# fountainPCB_v3.net
KiCad netlist of a schematic drawn in EAGLE
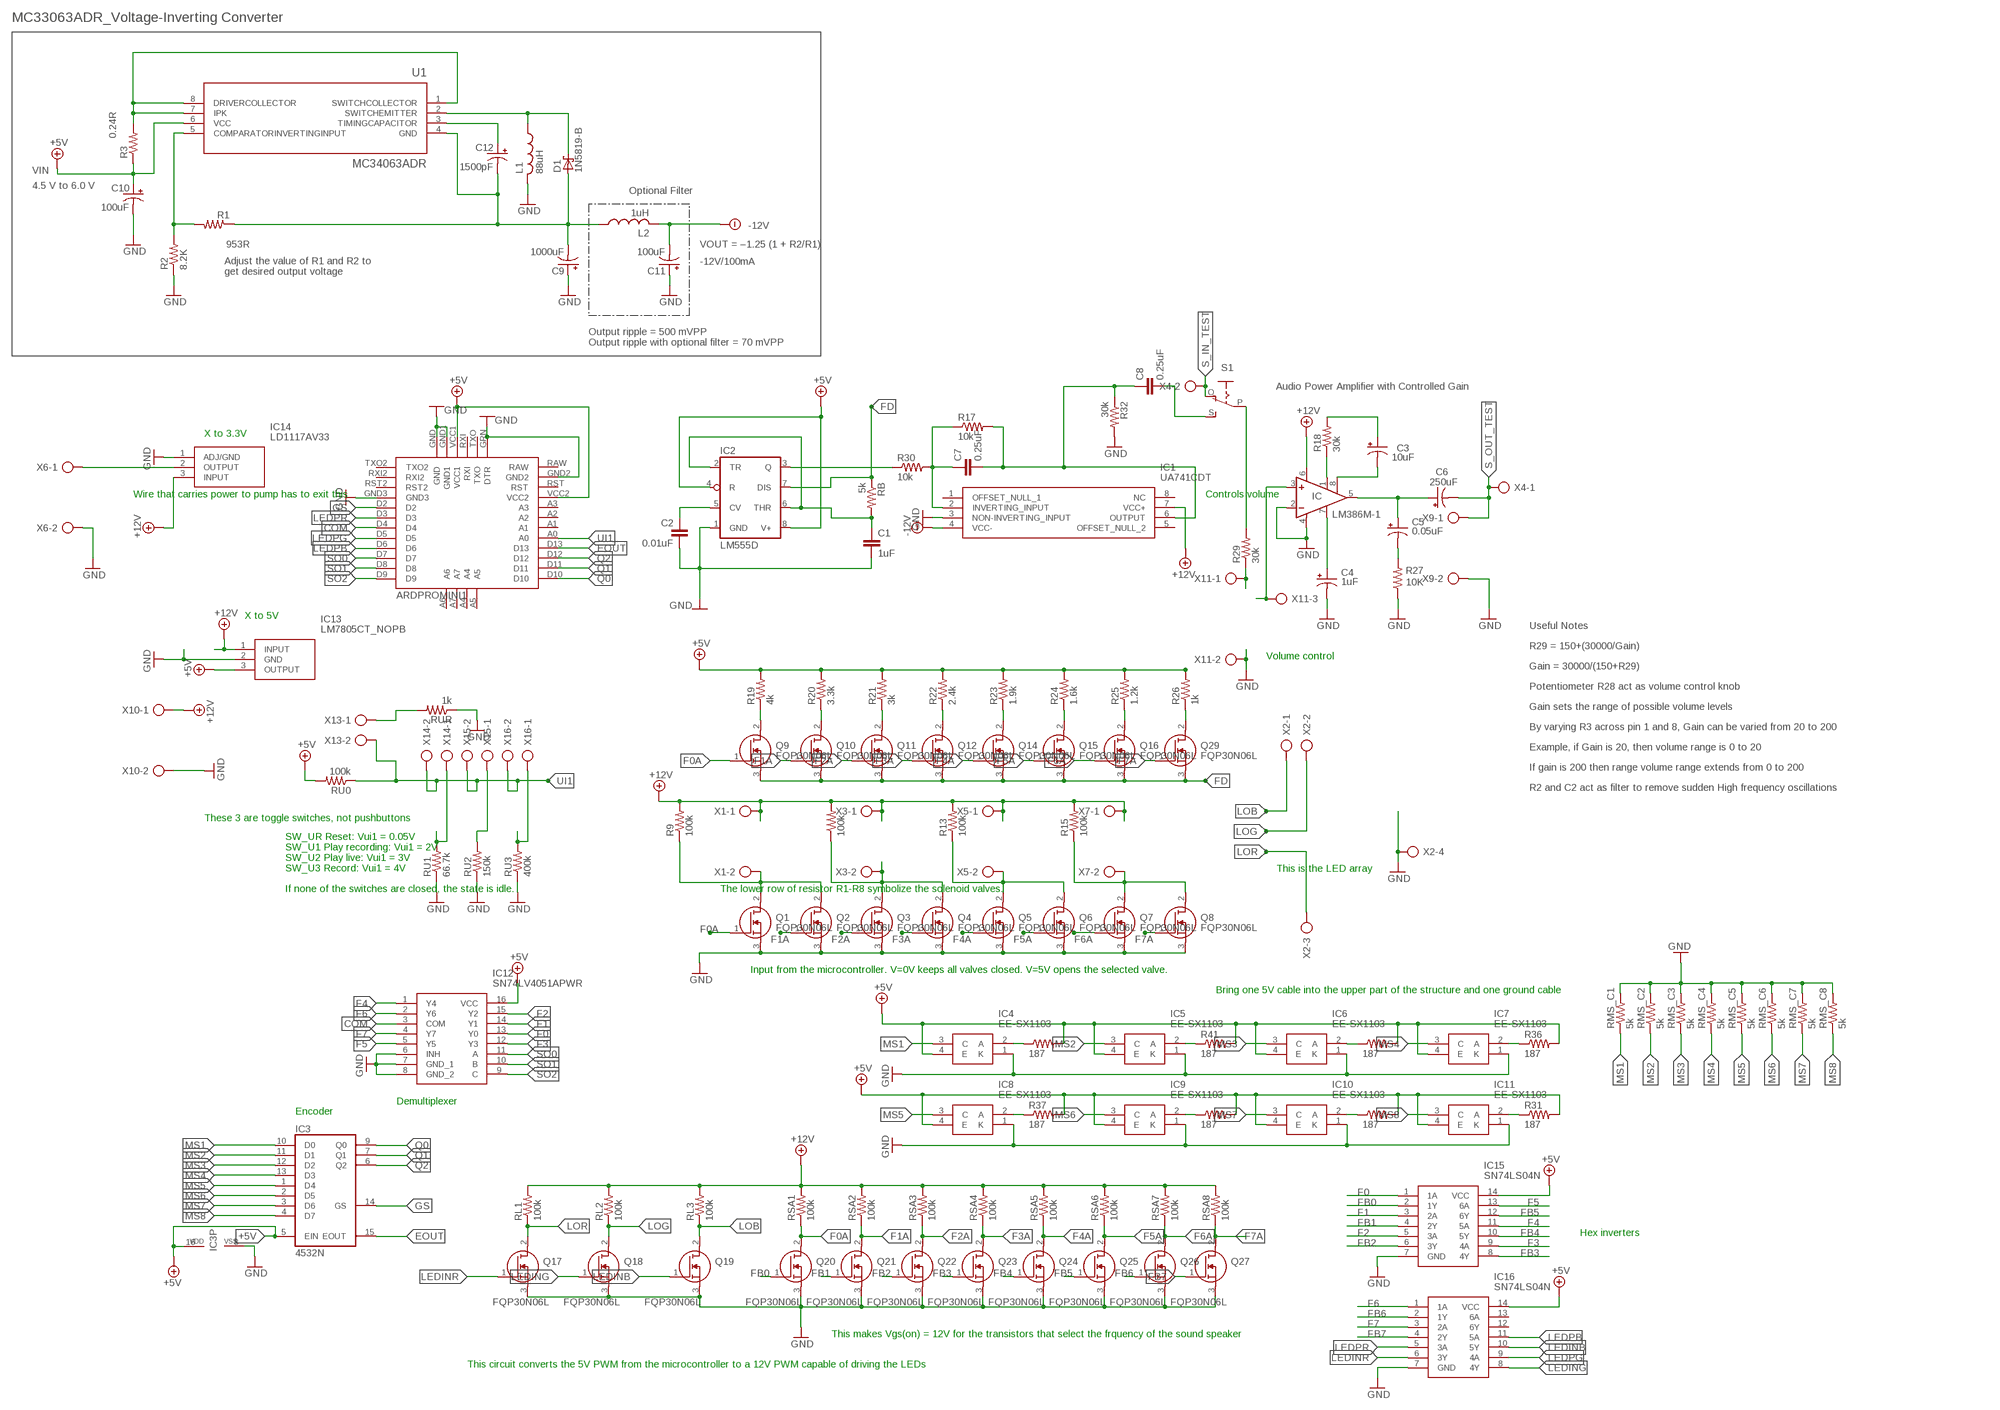
[diagram p0: schematic, sheet 1]

(export (version "E")
  (design (tool "Eeschema 10.0.6"))
  (components
    (comp (ref "ARDPROMINI1")
      (value "ARDUINOPROMINI")
      (footprint "eagle-import:ARDUINOPROMINI")
      (libsource (lib "eagle-import") (part "ARDUINOPROMINI"))
    )
    (comp (ref "C1")
      (value "1uF")
      (footprint "eagle-import:C0805")
      (libsource (lib "eagle-import") (part "C-EUC0805"))
    )
    (comp (ref "C2")
      (value "0.01uF")
      (footprint "eagle-import:C0805")
      (libsource (lib "eagle-import") (part "C-EUC0805"))
    )
    (comp (ref "C3")
      (value "10uF")
      (footprint "eagle-import:085CS_1AR")
      (fields (field (name "SPICEPREFIX") "C"))
      (libsource (lib "eagle-import") (part "resistor_348_CPOL-US085CS-1AR"))
    )
    (comp (ref "C4")
      (value "1uF")
      (footprint "eagle-import:085CS_1AR")
      (fields (field (name "SPICEPREFIX") "C"))
      (libsource (lib "eagle-import") (part "resistor_348_CPOL-US085CS-1AR"))
    )
    (comp (ref "C5")
      (value "0.05uF")
      (footprint "eagle-import:085CS_1AR")
      (fields (field (name "SPICEPREFIX") "C"))
      (libsource (lib "eagle-import") (part "resistor_348_CPOL-US085CS-1AR"))
    )
    (comp (ref "C6")
      (value "250uF")
      (footprint "eagle-import:085CS_1AR")
      (fields (field (name "SPICEPREFIX") "C"))
      (libsource (lib "eagle-import") (part "resistor_348_CPOL-US085CS-1AR"))
    )
    (comp (ref "C7")
      (value "0.25uF")
      (footprint "eagle-import:C0805")
      (fields (field (name "SPICEPREFIX") "C"))
      (libsource (lib "eagle-import") (part "C-EUC0805"))
    )
    (comp (ref "C8")
      (value "0.25uF")
      (footprint "eagle-import:C0805")
      (fields (field (name "SPICEPREFIX") "C"))
      (libsource (lib "eagle-import") (part "C-EUC0805"))
    )
    (comp (ref "C9")
      (value "1000uF")
      (footprint "eagle-import:E7,5-16")
      (libsource (lib "eagle-import") (part "CPOL-USE7.5-16"))
    )
    (comp (ref "C10")
      (value "100uF")
      (footprint "eagle-import:E2,5-6E")
      (libsource (lib "eagle-import") (part "CPOL-USE2,5-6E"))
    )
    (comp (ref "C11")
      (value "100uF")
      (footprint "eagle-import:E2,5-6E")
      (libsource (lib "eagle-import") (part "CPOL-USE2,5-6E"))
    )
    (comp (ref "C12")
      (value "1500pF")
      (footprint "eagle-import:E2,5-6E")
      (libsource (lib "eagle-import") (part "CPOL-USE2,5-6E"))
    )
    (comp (ref "D1")
      (value "1N5819-B")
      (footprint "eagle-import:DO41-7.6")
      (libsource (lib "eagle-import") (part "1N5819-B"))
    )
    (comp (ref "IC")
      (value "LM386M-1")
      (footprint "eagle-import:SO08")
      (fields (field (name "SPICEPREFIX") "X"))
      (libsource (lib "eagle-import") (part "LM386?-M1"))
    )
    (comp (ref "IC1")
      (value "UA741CDT")
      (footprint "eagle-import:SOIC127P600X175-8N")
      (fields (field (name "MOUSER_PART_NUMBER") "511-UA741CDT") (field (name "SPICEPREFIX") "X"))
      (libsource (lib "eagle-import") (part "UA741CDT"))
    )
    (comp (ref "IC2")
      (value "LM555D")
      (footprint "eagle-import:SO08")
      (fields (field (name "SPICEPREFIX") "X"))
      (libsource (lib "eagle-import") (part "555DLM"))
    )
    (comp (ref "IC3")
      (value "4532N")
      (footprint "eagle-import:DIL16")
      (fields (field (name "SPICEPREFIX") "X"))
      (libsource (lib "eagle-import") (part "4532N"))
    )
    (comp (ref "IC4")
      (value "EE-SX1103")
      (footprint "eagle-import:EESX1103")
      (fields (field (name "MOUSER_PART_NUMBER") "653-EE-SX1103"))
      (libsource (lib "eagle-import") (part "EE-SX1103"))
    )
    (comp (ref "IC5")
      (value "EE-SX1103")
      (footprint "eagle-import:EESX1103")
      (fields (field (name "MOUSER_PART_NUMBER") "653-EE-SX1103"))
      (libsource (lib "eagle-import") (part "EE-SX1103"))
    )
    (comp (ref "IC6")
      (value "EE-SX1103")
      (footprint "eagle-import:EESX1103")
      (fields (field (name "MOUSER_PART_NUMBER") "653-EE-SX1103"))
      (libsource (lib "eagle-import") (part "EE-SX1103"))
    )
    (comp (ref "IC7")
      (value "EE-SX1103")
      (footprint "eagle-import:EESX1103")
      (fields (field (name "MOUSER_PART_NUMBER") "653-EE-SX1103"))
      (libsource (lib "eagle-import") (part "EE-SX1103"))
    )
    (comp (ref "IC8")
      (value "EE-SX1103")
      (footprint "eagle-import:EESX1103")
      (fields (field (name "MOUSER_PART_NUMBER") "653-EE-SX1103"))
      (libsource (lib "eagle-import") (part "EE-SX1103"))
    )
    (comp (ref "IC9")
      (value "EE-SX1103")
      (footprint "eagle-import:EESX1103")
      (fields (field (name "MOUSER_PART_NUMBER") "653-EE-SX1103"))
      (libsource (lib "eagle-import") (part "EE-SX1103"))
    )
    (comp (ref "IC10")
      (value "EE-SX1103")
      (footprint "eagle-import:EESX1103")
      (fields (field (name "MOUSER_PART_NUMBER") "653-EE-SX1103"))
      (libsource (lib "eagle-import") (part "EE-SX1103"))
    )
    (comp (ref "IC11")
      (value "EE-SX1103")
      (footprint "eagle-import:EESX1103")
      (fields (field (name "MOUSER_PART_NUMBER") "653-EE-SX1103"))
      (libsource (lib "eagle-import") (part "EE-SX1103"))
    )
    (comp (ref "IC12")
      (value "SN74LV4051APWR")
      (footprint "eagle-import:SOP65P640X120-16N")
      (fields (field (name "MOUSER_PART_NUMBER") "595-SN74LV4051APWR") (field (name "SPICEPREFIX") "X"))
      (libsource (lib "eagle-import") (part "SN74LV4051APWR"))
    )
    (comp (ref "IC13")
      (value "LM7805CT_NOPB")
      (footprint "eagle-import:TO254P470X1028X1955-3P")
      (fields
        (field (name "MANUFACTURER_PART_NUMBER") "LM7805CT/NOPB")
        (field (name "MOUSER_PART_NUMBER") "926-LM7805CT/NOPB")
      )
      (libsource (lib "eagle-import") (part "LM7805CT_NOPB"))
    )
    (comp (ref "IC14")
      (value "LD1117AV33")
      (footprint "eagle-import:TO255P460X1020X2008-3P")
      (fields (field (name "MOUSER_PART_NUMBER") "511-LD1117AV33"))
      (libsource (lib "eagle-import") (part "LD1117AV33"))
    )
    (comp (ref "IC15")
      (value "SN74LS04N")
      (footprint "eagle-import:DIP794W53P254L1930H508Q14N")
      (fields (field (name "MOUSER_PART_NUMBER") "595-SN74LS04N") (field (name "SPICEPREFIX") "X"))
      (libsource (lib "eagle-import") (part "SN74LS04N"))
    )
    (comp (ref "IC16")
      (value "SN74LS04N")
      (footprint "eagle-import:DIP794W53P254L1930H508Q14N")
      (fields (field (name "MOUSER_PART_NUMBER") "595-SN74LS04N") (field (name "SPICEPREFIX") "X"))
      (libsource (lib "eagle-import") (part "SN74LS04N"))
    )
    (comp (ref "L1")
      (value "88uH")
      (footprint "eagle-import:L3216C")
      (libsource (lib "eagle-import") (part "L-USL3216C"))
    )
    (comp (ref "L2")
      (value "1uH")
      (footprint "eagle-import:L3216C")
      (libsource (lib "eagle-import") (part "L-USL3216C"))
    )
    (comp (ref "Q1")
      (value "FQP30N06L")
      (footprint "eagle-import:TO254P470X1016X2019-3P")
      (fields (field (name "MOUSER_PART_NUMBER") "512-FQP30N06L"))
      (libsource (lib "eagle-import") (part "FQP30N06L"))
    )
    (comp (ref "Q2")
      (value "FQP30N06L")
      (footprint "eagle-import:TO254P470X1016X2019-3P")
      (fields (field (name "MOUSER_PART_NUMBER") "512-FQP30N06L"))
      (libsource (lib "eagle-import") (part "FQP30N06L"))
    )
    (comp (ref "Q3")
      (value "FQP30N06L")
      (footprint "eagle-import:TO254P470X1016X2019-3P")
      (fields (field (name "MOUSER_PART_NUMBER") "512-FQP30N06L"))
      (libsource (lib "eagle-import") (part "FQP30N06L"))
    )
    (comp (ref "Q4")
      (value "FQP30N06L")
      (footprint "eagle-import:TO254P470X1016X2019-3P")
      (fields (field (name "MOUSER_PART_NUMBER") "512-FQP30N06L"))
      (libsource (lib "eagle-import") (part "FQP30N06L"))
    )
    (comp (ref "Q5")
      (value "FQP30N06L")
      (footprint "eagle-import:TO254P470X1016X2019-3P")
      (fields (field (name "MOUSER_PART_NUMBER") "512-FQP30N06L"))
      (libsource (lib "eagle-import") (part "FQP30N06L"))
    )
    (comp (ref "Q6")
      (value "FQP30N06L")
      (footprint "eagle-import:TO254P470X1016X2019-3P")
      (fields (field (name "MOUSER_PART_NUMBER") "512-FQP30N06L"))
      (libsource (lib "eagle-import") (part "FQP30N06L"))
    )
    (comp (ref "Q7")
      (value "FQP30N06L")
      (footprint "eagle-import:TO254P470X1016X2019-3P")
      (fields (field (name "MOUSER_PART_NUMBER") "512-FQP30N06L"))
      (libsource (lib "eagle-import") (part "FQP30N06L"))
    )
    (comp (ref "Q8")
      (value "FQP30N06L")
      (footprint "eagle-import:TO254P470X1016X2019-3P")
      (fields (field (name "MOUSER_PART_NUMBER") "512-FQP30N06L"))
      (libsource (lib "eagle-import") (part "FQP30N06L"))
    )
    (comp (ref "Q9")
      (value "FQP30N06L")
      (footprint "eagle-import:TO254P470X1016X2019-3P")
      (fields (field (name "MOUSER_PART_NUMBER") "512-FQP30N06L"))
      (libsource (lib "eagle-import") (part "FQP30N06L"))
    )
    (comp (ref "Q10")
      (value "FQP30N06L")
      (footprint "eagle-import:TO254P470X1016X2019-3P")
      (fields (field (name "MOUSER_PART_NUMBER") "512-FQP30N06L"))
      (libsource (lib "eagle-import") (part "FQP30N06L"))
    )
    (comp (ref "Q11")
      (value "FQP30N06L")
      (footprint "eagle-import:TO254P470X1016X2019-3P")
      (fields (field (name "MOUSER_PART_NUMBER") "512-FQP30N06L"))
      (libsource (lib "eagle-import") (part "FQP30N06L"))
    )
    (comp (ref "Q12")
      (value "FQP30N06L")
      (footprint "eagle-import:TO254P470X1016X2019-3P")
      (fields (field (name "MOUSER_PART_NUMBER") "512-FQP30N06L"))
      (libsource (lib "eagle-import") (part "FQP30N06L"))
    )
    (comp (ref "Q14")
      (value "FQP30N06L")
      (footprint "eagle-import:TO254P470X1016X2019-3P")
      (fields (field (name "MOUSER_PART_NUMBER") "512-FQP30N06L"))
      (libsource (lib "eagle-import") (part "FQP30N06L"))
    )
    (comp (ref "Q15")
      (value "FQP30N06L")
      (footprint "eagle-import:TO254P470X1016X2019-3P")
      (fields (field (name "MOUSER_PART_NUMBER") "512-FQP30N06L"))
      (libsource (lib "eagle-import") (part "FQP30N06L"))
    )
    (comp (ref "Q16")
      (value "FQP30N06L")
      (footprint "eagle-import:TO254P470X1016X2019-3P")
      (fields (field (name "MOUSER_PART_NUMBER") "512-FQP30N06L"))
      (libsource (lib "eagle-import") (part "FQP30N06L"))
    )
    (comp (ref "Q17")
      (value "FQP30N06L")
      (footprint "eagle-import:TO254P470X1016X2019-3P")
      (fields (field (name "MOUSER_PART_NUMBER") "512-FQP30N06L"))
      (libsource (lib "eagle-import") (part "FQP30N06L"))
    )
    (comp (ref "Q18")
      (value "FQP30N06L")
      (footprint "eagle-import:TO254P470X1016X2019-3P")
      (fields (field (name "MOUSER_PART_NUMBER") "512-FQP30N06L"))
      (libsource (lib "eagle-import") (part "FQP30N06L"))
    )
    (comp (ref "Q19")
      (value "FQP30N06L")
      (footprint "eagle-import:TO254P470X1016X2019-3P")
      (fields (field (name "MOUSER_PART_NUMBER") "512-FQP30N06L"))
      (libsource (lib "eagle-import") (part "FQP30N06L"))
    )
    (comp (ref "Q20")
      (value "FQP30N06L")
      (footprint "eagle-import:TO254P470X1016X2019-3P")
      (fields (field (name "MOUSER_PART_NUMBER") "512-FQP30N06L"))
      (libsource (lib "eagle-import") (part "FQP30N06L"))
    )
    (comp (ref "Q21")
      (value "FQP30N06L")
      (footprint "eagle-import:TO254P470X1016X2019-3P")
      (fields (field (name "MOUSER_PART_NUMBER") "512-FQP30N06L"))
      (libsource (lib "eagle-import") (part "FQP30N06L"))
    )
    (comp (ref "Q22")
      (value "FQP30N06L")
      (footprint "eagle-import:TO254P470X1016X2019-3P")
      (fields (field (name "MOUSER_PART_NUMBER") "512-FQP30N06L"))
      (libsource (lib "eagle-import") (part "FQP30N06L"))
    )
    (comp (ref "Q23")
      (value "FQP30N06L")
      (footprint "eagle-import:TO254P470X1016X2019-3P")
      (fields (field (name "MOUSER_PART_NUMBER") "512-FQP30N06L"))
      (libsource (lib "eagle-import") (part "FQP30N06L"))
    )
    (comp (ref "Q24")
      (value "FQP30N06L")
      (footprint "eagle-import:TO254P470X1016X2019-3P")
      (fields (field (name "MOUSER_PART_NUMBER") "512-FQP30N06L"))
      (libsource (lib "eagle-import") (part "FQP30N06L"))
    )
    (comp (ref "Q25")
      (value "FQP30N06L")
      (footprint "eagle-import:TO254P470X1016X2019-3P")
      (fields (field (name "MOUSER_PART_NUMBER") "512-FQP30N06L"))
      (libsource (lib "eagle-import") (part "FQP30N06L"))
    )
    (comp (ref "Q26")
      (value "FQP30N06L")
      (footprint "eagle-import:TO254P470X1016X2019-3P")
      (fields (field (name "MOUSER_PART_NUMBER") "512-FQP30N06L"))
      (libsource (lib "eagle-import") (part "FQP30N06L"))
    )
    (comp (ref "Q27")
      (value "FQP30N06L")
      (footprint "eagle-import:TO254P470X1016X2019-3P")
      (fields (field (name "MOUSER_PART_NUMBER") "512-FQP30N06L"))
      (libsource (lib "eagle-import") (part "FQP30N06L"))
    )
    (comp (ref "Q29")
      (value "FQP30N06L")
      (footprint "eagle-import:TO254P470X1016X2019-3P")
      (fields (field (name "MOUSER_PART_NUMBER") "512-FQP30N06L"))
      (libsource (lib "eagle-import") (part "FQP30N06L"))
    )
    (comp (ref "R1")
      (value "953R")
      (footprint "eagle-import:M0805")
      (libsource (lib "eagle-import") (part "R-US_M0805"))
    )
    (comp (ref "R2")
      (value "8.2K")
      (footprint "eagle-import:M0805")
      (libsource (lib "eagle-import") (part "R-US_M0805"))
    )
    (comp (ref "R3")
      (value "0.24R")
      (footprint "eagle-import:M0805")
      (libsource (lib "eagle-import") (part "R-US_M0805"))
    )
    (comp (ref "R9")
      (value "100k")
      (footprint "eagle-import:R0805")
      (libsource (lib "eagle-import") (part "R-US_R0805"))
    )
    (comp (ref "R11")
      (value "100k")
      (footprint "eagle-import:R0805")
      (libsource (lib "eagle-import") (part "R-US_R0805"))
    )
    (comp (ref "R13")
      (value "100k")
      (footprint "eagle-import:R0805")
      (libsource (lib "eagle-import") (part "R-US_R0805"))
    )
    (comp (ref "R15")
      (value "100k")
      (footprint "eagle-import:R0805")
      (libsource (lib "eagle-import") (part "R-US_R0805"))
    )
    (comp (ref "R17")
      (value "10k")
      (footprint "eagle-import:R0805")
      (libsource (lib "eagle-import") (part "R-US_R0805"))
    )
    (comp (ref "R18")
      (value "30k")
      (footprint "eagle-import:R0805")
      (libsource (lib "eagle-import") (part "R-US_R0805"))
    )
    (comp (ref "R19")
      (value "4k")
      (footprint "eagle-import:R0805")
      (libsource (lib "eagle-import") (part "R-US_R0805"))
    )
    (comp (ref "R20")
      (value "3.3k")
      (footprint "eagle-import:R0805")
      (libsource (lib "eagle-import") (part "R-US_R0805"))
    )
    (comp (ref "R21")
      (value "3k")
      (footprint "eagle-import:R0805")
      (libsource (lib "eagle-import") (part "R-US_R0805"))
    )
    (comp (ref "R22")
      (value "2.4k")
      (footprint "eagle-import:R0805")
      (libsource (lib "eagle-import") (part "R-US_R0805"))
    )
    (comp (ref "R23")
      (value "1.9k")
      (footprint "eagle-import:R0805")
      (libsource (lib "eagle-import") (part "R-US_R0805"))
    )
    (comp (ref "R24")
      (value "1.6k")
      (footprint "eagle-import:R0805")
      (libsource (lib "eagle-import") (part "R-US_R0805"))
    )
    (comp (ref "R25")
      (value "1.2k")
      (footprint "eagle-import:R0805")
      (libsource (lib "eagle-import") (part "R-US_R0805"))
    )
    (comp (ref "R26")
      (value "1k")
      (footprint "eagle-import:R0805")
      (libsource (lib "eagle-import") (part "R-US_R0805"))
    )
    (comp (ref "R27")
      (value "10K")
      (footprint "eagle-import:M0805")
      (fields (field (name "SPICEPREFIX") "R"))
      (libsource (lib "eagle-import") (part "resistor_348_R-US_M0805"))
    )
    (comp (ref "R29")
      (value "30k")
      (footprint "eagle-import:R0805")
      (libsource (lib "eagle-import") (part "R-US_R0805"))
    )
    (comp (ref "R30")
      (value "10k")
      (footprint "eagle-import:R0805")
      (libsource (lib "eagle-import") (part "R-US_R0805"))
    )
    (comp (ref "R31")
      (value "187")
      (footprint "eagle-import:R0805")
      (libsource (lib "eagle-import") (part "R-US_R0805"))
    )
    (comp (ref "R32")
      (value "30k")
      (footprint "eagle-import:R0805")
      (libsource (lib "eagle-import") (part "R-US_R0805"))
    )
    (comp (ref "R34")
      (value "187")
      (footprint "eagle-import:R0805")
      (libsource (lib "eagle-import") (part "R-US_R0805"))
    )
    (comp (ref "R36")
      (value "187")
      (footprint "eagle-import:R0805")
      (libsource (lib "eagle-import") (part "R-US_R0805"))
    )
    (comp (ref "R37")
      (value "187")
      (footprint "eagle-import:R0805")
      (libsource (lib "eagle-import") (part "R-US_R0805"))
    )
    (comp (ref "R40")
      (value "187")
      (footprint "eagle-import:R0805")
      (libsource (lib "eagle-import") (part "R-US_R0805"))
    )
    (comp (ref "R41")
      (value "187")
      (footprint "eagle-import:R0805")
      (libsource (lib "eagle-import") (part "R-US_R0805"))
    )
    (comp (ref "R42")
      (value "187")
      (footprint "eagle-import:R0805")
      (libsource (lib "eagle-import") (part "R-US_R0805"))
    )
    (comp (ref "R44")
      (value "187")
      (footprint "eagle-import:R0805")
      (libsource (lib "eagle-import") (part "R-US_R0805"))
    )
    (comp (ref "RB")
      (value "5k")
      (footprint "eagle-import:R0805")
      (libsource (lib "eagle-import") (part "R-US_R0805"))
    )
    (comp (ref "RL1")
      (value "100k")
      (footprint "eagle-import:R0805")
      (libsource (lib "eagle-import") (part "R-US_R0805"))
    )
    (comp (ref "RL2")
      (value "100k")
      (footprint "eagle-import:R0805")
      (libsource (lib "eagle-import") (part "R-US_R0805"))
    )
    (comp (ref "RL3")
      (value "100k")
      (footprint "eagle-import:R0805")
      (libsource (lib "eagle-import") (part "R-US_R0805"))
    )
    (comp (ref "RMS_C1")
      (value "5k")
      (footprint "eagle-import:R0805")
      (libsource (lib "eagle-import") (part "R-US_R0805"))
    )
    (comp (ref "RMS_C2")
      (value "5k")
      (footprint "eagle-import:R0805")
      (libsource (lib "eagle-import") (part "R-US_R0805"))
    )
    (comp (ref "RMS_C3")
      (value "5k")
      (footprint "eagle-import:R0805")
      (libsource (lib "eagle-import") (part "R-US_R0805"))
    )
    (comp (ref "RMS_C4")
      (value "5k")
      (footprint "eagle-import:R0805")
      (libsource (lib "eagle-import") (part "R-US_R0805"))
    )
    (comp (ref "RMS_C5")
      (value "5k")
      (footprint "eagle-import:R0805")
      (libsource (lib "eagle-import") (part "R-US_R0805"))
    )
    (comp (ref "RMS_C6")
      (value "5k")
      (footprint "eagle-import:R0805")
      (libsource (lib "eagle-import") (part "R-US_R0805"))
    )
    (comp (ref "RMS_C7")
      (value "5k")
      (footprint "eagle-import:R0805")
      (libsource (lib "eagle-import") (part "R-US_R0805"))
    )
    (comp (ref "RMS_C8")
      (value "5k")
      (footprint "eagle-import:R0805")
      (libsource (lib "eagle-import") (part "R-US_R0805"))
    )
    (comp (ref "RSA1")
      (value "100k")
      (footprint "eagle-import:R0805")
      (libsource (lib "eagle-import") (part "R-US_R0805"))
    )
    (comp (ref "RSA2")
      (value "100k")
      (footprint "eagle-import:R0805")
      (libsource (lib "eagle-import") (part "R-US_R0805"))
    )
    (comp (ref "RSA3")
      (value "100k")
      (footprint "eagle-import:R0805")
      (libsource (lib "eagle-import") (part "R-US_R0805"))
    )
    (comp (ref "RSA4")
      (value "100k")
      (footprint "eagle-import:R0805")
      (libsource (lib "eagle-import") (part "R-US_R0805"))
    )
    (comp (ref "RSA5")
      (value "100k")
      (footprint "eagle-import:R0805")
      (libsource (lib "eagle-import") (part "R-US_R0805"))
    )
    (comp (ref "RSA6")
      (value "100k")
      (footprint "eagle-import:R0805")
      (libsource (lib "eagle-import") (part "R-US_R0805"))
    )
    (comp (ref "RSA7")
      (value "100k")
      (footprint "eagle-import:R0805")
      (libsource (lib "eagle-import") (part "R-US_R0805"))
    )
    (comp (ref "RSA8")
      (value "100k")
      (footprint "eagle-import:R0805")
      (libsource (lib "eagle-import") (part "R-US_R0805"))
    )
    (comp (ref "RU0")
      (value "100k")
      (footprint "eagle-import:R0805")
      (libsource (lib "eagle-import") (part "R-US_R0805"))
    )
    (comp (ref "RU1")
      (value "66.7k")
      (footprint "eagle-import:R0805")
      (libsource (lib "eagle-import") (part "R-US_R0805"))
    )
    (comp (ref "RU2")
      (value "150k")
      (footprint "eagle-import:R0805")
      (libsource (lib "eagle-import") (part "R-US_R0805"))
    )
    (comp (ref "RU3")
      (value "400k")
      (footprint "eagle-import:R0805")
      (libsource (lib "eagle-import") (part "R-US_R0805"))
    )
    (comp (ref "RUR")
      (value "1k")
      (footprint "eagle-import:R0805")
      (libsource (lib "eagle-import") (part "R-US_R0805"))
    )
    (comp (ref "S1")
      (value "EG1218S")
      (footprint "eagle-import:EG1218")
      (fields (field (name "SPICEPREFIX") "J"))
      (libsource (lib "eagle-import") (part "EG1218S"))
    )
    (comp (ref "U1")
      (value "MC34063ADR")
      (footprint "eagle-import:D8")
      (libsource (lib "eagle-import") (part "MC34063ADR"))
    )
    (comp (ref "X1")
      (value "AK300/2")
      (footprint "eagle-import:AK300_2")
      (fields (field (name "SPICEPREFIX") "X"))
      (libsource (lib "eagle-import") (part "AK300/2"))
    )
    (comp (ref "X2")
      (value "AK300/4")
      (footprint "eagle-import:AK300_4")
      (libsource (lib "eagle-import") (part "AK300/4"))
    )
    (comp (ref "X3")
      (value "AK300/2")
      (footprint "eagle-import:AK300_2")
      (fields (field (name "SPICEPREFIX") "X"))
      (libsource (lib "eagle-import") (part "AK300/2"))
    )
    (comp (ref "X4")
      (value "AK300/2")
      (footprint "eagle-import:AK300_2")
      (libsource (lib "eagle-import") (part "AK300/2"))
    )
    (comp (ref "X5")
      (value "AK300/2")
      (footprint "eagle-import:AK300_2")
      (fields (field (name "SPICEPREFIX") "X"))
      (libsource (lib "eagle-import") (part "AK300/2"))
    )
    (comp (ref "X6")
      (value "AK300/2")
      (footprint "eagle-import:AK300_2")
      (fields (field (name "SPICEPREFIX") "X"))
      (libsource (lib "eagle-import") (part "AK300/2"))
    )
    (comp (ref "X7")
      (value "AK300/2")
      (footprint "eagle-import:AK300_2")
      (fields (field (name "SPICEPREFIX") "X"))
      (libsource (lib "eagle-import") (part "AK300/2"))
    )
    (comp (ref "X9")
      (value "AK300/2")
      (footprint "eagle-import:AK300_2")
      (fields (field (name "SPICEPREFIX") "X"))
      (libsource (lib "eagle-import") (part "AK300/2"))
    )
    (comp (ref "X10")
      (value "AK300/2")
      (footprint "eagle-import:AK300_2")
      (fields (field (name "SPICEPREFIX") "X"))
      (libsource (lib "eagle-import") (part "AK300/2"))
    )
    (comp (ref "X11")
      (value "AK300/3")
      (footprint "eagle-import:AK300_3")
      (fields (field (name "SPICEPREFIX") "X"))
      (libsource (lib "eagle-import") (part "AK300/3"))
    )
    (comp (ref "X13")
      (value "AK300/2")
      (footprint "eagle-import:AK300_2")
      (fields (field (name "SPICEPREFIX") "X"))
      (libsource (lib "eagle-import") (part "AK300/2"))
    )
    (comp (ref "X14")
      (value "AK300/2")
      (footprint "eagle-import:AK300_2")
      (fields (field (name "SPICEPREFIX") "X"))
      (libsource (lib "eagle-import") (part "AK300/2"))
    )
    (comp (ref "X15")
      (value "AK300/2")
      (footprint "eagle-import:AK300_2")
      (fields (field (name "SPICEPREFIX") "X"))
      (libsource (lib "eagle-import") (part "AK300/2"))
    )
    (comp (ref "X16")
      (value "AK300/2")
      (footprint "eagle-import:AK300_2")
      (fields (field (name "SPICEPREFIX") "X"))
      (libsource (lib "eagle-import") (part "AK300/2"))
    )
  )
  (nets
    (net (code "1") (name "+5V") (class "Default")
      (node (ref "ARDPROMINI1") (pin "VCC1") (pinfunction "VCC1_VCC1") (pintype "bidirectional"))
      (node (ref "ARDPROMINI1") (pin "VCC2") (pinfunction "VCC2_VCC2") (pintype "bidirectional"))
      (node (ref "C10") (pin "+") (pinfunction "+_+") (pintype "passive"))
      (node (ref "IC10") (pin "4") (pinfunction "E_4") (pintype "bidirectional"))
      (node (ref "IC11") (pin "4") (pinfunction "E_4") (pintype "bidirectional"))
      (node (ref "IC12") (pin "16") (pinfunction "VCC_16") (pintype "bidirectional"))
      (node (ref "IC13") (pin "3") (pinfunction "OUTPUT_3") (pintype "bidirectional"))
      (node (ref "IC15") (pin "14") (pinfunction "VCC_14") (pintype "bidirectional"))
      (node (ref "IC16") (pin "14") (pinfunction "VCC_14") (pintype "bidirectional"))
      (node (ref "IC2") (pin "4") (pinfunction "R_4") (pintype "input"))
      (node (ref "IC2") (pin "8") (pinfunction "V+_8") (pintype "power_in"))
      (node (ref "IC3") (pin "16") (pinfunction "VDD_16") (pintype "power_in"))
      (node (ref "IC3") (pin "5") (pinfunction "EIN_5") (pintype "input"))
      (node (ref "IC4") (pin "4") (pinfunction "E_4") (pintype "bidirectional"))
      (node (ref "IC5") (pin "4") (pinfunction "E_4") (pintype "bidirectional"))
      (node (ref "IC6") (pin "4") (pinfunction "E_4") (pintype "bidirectional"))
      (node (ref "IC7") (pin "4") (pinfunction "E_4") (pintype "bidirectional"))
      (node (ref "IC8") (pin "4") (pinfunction "E_4") (pintype "bidirectional"))
      (node (ref "IC9") (pin "4") (pinfunction "E_4") (pintype "bidirectional"))
      (node (ref "R19") (pin "2") (pinfunction "2_2") (pintype "passive"))
      (node (ref "R20") (pin "2") (pinfunction "2_2") (pintype "passive"))
      (node (ref "R21") (pin "2") (pinfunction "2_2") (pintype "passive"))
      (node (ref "R22") (pin "2") (pinfunction "2_2") (pintype "passive"))
      (node (ref "R23") (pin "2") (pinfunction "2_2") (pintype "passive"))
      (node (ref "R24") (pin "2") (pinfunction "2_2") (pintype "passive"))
      (node (ref "R25") (pin "2") (pinfunction "2_2") (pintype "passive"))
      (node (ref "R26") (pin "2") (pinfunction "2_2") (pintype "passive"))
      (node (ref "R3") (pin "1") (pinfunction "1_1") (pintype "passive"))
      (node (ref "R31") (pin "2") (pinfunction "2_2") (pintype "passive"))
      (node (ref "R34") (pin "2") (pinfunction "2_2") (pintype "passive"))
      (node (ref "R36") (pin "2") (pinfunction "2_2") (pintype "passive"))
      (node (ref "R37") (pin "2") (pinfunction "2_2") (pintype "passive"))
      (node (ref "R40") (pin "2") (pinfunction "2_2") (pintype "passive"))
      (node (ref "R41") (pin "2") (pinfunction "2_2") (pintype "passive"))
      (node (ref "R42") (pin "2") (pinfunction "2_2") (pintype "passive"))
      (node (ref "R44") (pin "2") (pinfunction "2_2") (pintype "passive"))
      (node (ref "RU0") (pin "2") (pinfunction "2_2") (pintype "passive"))
      (node (ref "U1") (pin "6") (pinfunction "VCC_6") (pintype "power_in"))
    )
    (net (code "2") (name "+12V") (class "Default")
      (node (ref "IC") (pin "6") (pinfunction "VS_6") (pintype "power_in"))
      (node (ref "IC1") (pin "7") (pinfunction "VCC+_7") (pintype "bidirectional"))
      (node (ref "IC13") (pin "1") (pinfunction "INPUT_1") (pintype "bidirectional"))
      (node (ref "IC14") (pin "3") (pinfunction "INPUT_3") (pintype "bidirectional"))
      (node (ref "R11") (pin "2") (pinfunction "2_2") (pintype "passive"))
      (node (ref "R13") (pin "2") (pinfunction "2_2") (pintype "passive"))
      (node (ref "R15") (pin "2") (pinfunction "2_2") (pintype "passive"))
      (node (ref "R9") (pin "2") (pinfunction "2_2") (pintype "passive"))
      (node (ref "RL1") (pin "2") (pinfunction "2_2") (pintype "passive"))
      (node (ref "RL2") (pin "2") (pinfunction "2_2") (pintype "passive"))
      (node (ref "RL3") (pin "2") (pinfunction "2_2") (pintype "passive"))
      (node (ref "RSA1") (pin "2") (pinfunction "2_2") (pintype "passive"))
      (node (ref "RSA2") (pin "2") (pinfunction "2_2") (pintype "passive"))
      (node (ref "RSA3") (pin "2") (pinfunction "2_2") (pintype "passive"))
      (node (ref "RSA4") (pin "2") (pinfunction "2_2") (pintype "passive"))
      (node (ref "RSA5") (pin "2") (pinfunction "2_2") (pintype "passive"))
      (node (ref "RSA6") (pin "2") (pinfunction "2_2") (pintype "passive"))
      (node (ref "RSA7") (pin "2") (pinfunction "2_2") (pintype "passive"))
      (node (ref "RSA8") (pin "2") (pinfunction "2_2") (pintype "passive"))
      (node (ref "X1") (pin "1") (pinfunction "KL_1") (pintype "passive"))
      (node (ref "X10") (pin "1") (pinfunction "KL_1") (pintype "passive"))
      (node (ref "X3") (pin "1") (pinfunction "KL_1") (pintype "passive"))
      (node (ref "X5") (pin "1") (pinfunction "KL_1") (pintype "passive"))
      (node (ref "X7") (pin "1") (pinfunction "KL_1") (pintype "passive"))
    )
    (net (code "3") (name "-12V") (class "Default")
      (node (ref "C11") (pin "-") (pinfunction "-_-") (pintype "passive"))
      (node (ref "IC1") (pin "4") (pinfunction "VCC-_4") (pintype "bidirectional"))
      (node (ref "L2") (pin "2") (pinfunction "2_2") (pintype "passive"))
    )
    (net (code "4") (name "COM") (class "Default")
      (node (ref "ARDPROMINI1") (pin "D4") (pinfunction "D4_D4") (pintype "bidirectional"))
      (node (ref "IC12") (pin "3") (pinfunction "COM_3") (pintype "bidirectional"))
    )
    (net (code "5") (name "EOUT") (class "Default")
      (node (ref "ARDPROMINI1") (pin "D13") (pinfunction "D13_D13") (pintype "bidirectional"))
      (node (ref "IC3") (pin "15") (pinfunction "EOUT_15") (pintype "output"))
    )
    (net (code "6") (name "F0") (class "Default")
      (node (ref "IC12") (pin "13") (pinfunction "Y0_13") (pintype "bidirectional"))
      (node (ref "IC15") (pin "1") (pinfunction "1A_1") (pintype "bidirectional"))
    )
    (net (code "7") (name "F0A") (class "Default")
      (node (ref "Q1") (pin "1") (pinfunction "G_1") (pintype "bidirectional"))
      (node (ref "Q20") (pin "2") (pinfunction "D_2") (pintype "bidirectional"))
      (node (ref "Q9") (pin "1") (pinfunction "G_1") (pintype "bidirectional"))
      (node (ref "RSA1") (pin "1") (pinfunction "1_1") (pintype "passive"))
    )
    (net (code "8") (name "F1") (class "Default")
      (node (ref "IC12") (pin "14") (pinfunction "Y1_14") (pintype "bidirectional"))
      (node (ref "IC15") (pin "3") (pinfunction "2A_3") (pintype "bidirectional"))
    )
    (net (code "9") (name "F1A") (class "Default")
      (node (ref "Q10") (pin "1") (pinfunction "G_1") (pintype "bidirectional"))
      (node (ref "Q2") (pin "1") (pinfunction "G_1") (pintype "bidirectional"))
      (node (ref "Q21") (pin "2") (pinfunction "D_2") (pintype "bidirectional"))
      (node (ref "RSA2") (pin "1") (pinfunction "1_1") (pintype "passive"))
    )
    (net (code "10") (name "F2") (class "Default")
      (node (ref "IC12") (pin "15") (pinfunction "Y2_15") (pintype "bidirectional"))
      (node (ref "IC15") (pin "5") (pinfunction "3A_5") (pintype "bidirectional"))
    )
    (net (code "11") (name "F2A") (class "Default")
      (node (ref "Q11") (pin "1") (pinfunction "G_1") (pintype "bidirectional"))
      (node (ref "Q22") (pin "2") (pinfunction "D_2") (pintype "bidirectional"))
      (node (ref "Q3") (pin "1") (pinfunction "G_1") (pintype "bidirectional"))
      (node (ref "RSA3") (pin "1") (pinfunction "1_1") (pintype "passive"))
    )
    (net (code "12") (name "F3") (class "Default")
      (node (ref "IC12") (pin "12") (pinfunction "Y3_12") (pintype "bidirectional"))
      (node (ref "IC15") (pin "9") (pinfunction "4A_9") (pintype "bidirectional"))
    )
    (net (code "13") (name "F3A") (class "Default")
      (node (ref "Q12") (pin "1") (pinfunction "G_1") (pintype "bidirectional"))
      (node (ref "Q23") (pin "2") (pinfunction "D_2") (pintype "bidirectional"))
      (node (ref "Q4") (pin "1") (pinfunction "G_1") (pintype "bidirectional"))
      (node (ref "RSA4") (pin "1") (pinfunction "1_1") (pintype "passive"))
    )
    (net (code "14") (name "F4") (class "Default")
      (node (ref "IC12") (pin "1") (pinfunction "Y4_1") (pintype "bidirectional"))
      (node (ref "IC15") (pin "11") (pinfunction "5A_11") (pintype "bidirectional"))
    )
    (net (code "15") (name "F4A") (class "Default")
      (node (ref "Q14") (pin "1") (pinfunction "G_1") (pintype "bidirectional"))
      (node (ref "Q24") (pin "2") (pinfunction "D_2") (pintype "bidirectional"))
      (node (ref "Q5") (pin "1") (pinfunction "G_1") (pintype "bidirectional"))
      (node (ref "RSA5") (pin "1") (pinfunction "1_1") (pintype "passive"))
    )
    (net (code "16") (name "F5") (class "Default")
      (node (ref "IC12") (pin "5") (pinfunction "Y5_5") (pintype "bidirectional"))
      (node (ref "IC15") (pin "13") (pinfunction "6A_13") (pintype "bidirectional"))
    )
    (net (code "17") (name "F5A") (class "Default")
      (node (ref "Q15") (pin "1") (pinfunction "G_1") (pintype "bidirectional"))
      (node (ref "Q25") (pin "2") (pinfunction "D_2") (pintype "bidirectional"))
      (node (ref "Q6") (pin "1") (pinfunction "G_1") (pintype "bidirectional"))
      (node (ref "RSA6") (pin "1") (pinfunction "1_1") (pintype "passive"))
    )
    (net (code "18") (name "F6") (class "Default")
      (node (ref "IC12") (pin "2") (pinfunction "Y6_2") (pintype "bidirectional"))
      (node (ref "IC16") (pin "1") (pinfunction "1A_1") (pintype "bidirectional"))
    )
    (net (code "19") (name "F6A") (class "Default")
      (node (ref "Q16") (pin "1") (pinfunction "G_1") (pintype "bidirectional"))
      (node (ref "Q26") (pin "2") (pinfunction "D_2") (pintype "bidirectional"))
      (node (ref "Q7") (pin "1") (pinfunction "G_1") (pintype "bidirectional"))
      (node (ref "RSA7") (pin "1") (pinfunction "1_1") (pintype "passive"))
    )
    (net (code "20") (name "F7") (class "Default")
      (node (ref "IC12") (pin "4") (pinfunction "Y7_4") (pintype "bidirectional"))
      (node (ref "IC16") (pin "3") (pinfunction "2A_3") (pintype "bidirectional"))
    )
    (net (code "21") (name "F7A") (class "Default")
      (node (ref "Q27") (pin "2") (pinfunction "D_2") (pintype "bidirectional"))
      (node (ref "Q29") (pin "1") (pinfunction "G_1") (pintype "bidirectional"))
      (node (ref "Q8") (pin "1") (pinfunction "G_1") (pintype "bidirectional"))
      (node (ref "RSA8") (pin "1") (pinfunction "1_1") (pintype "passive"))
    )
    (net (code "22") (name "FB0") (class "Default")
      (node (ref "IC15") (pin "2") (pinfunction "1Y_2") (pintype "bidirectional"))
      (node (ref "Q20") (pin "1") (pinfunction "G_1") (pintype "bidirectional"))
    )
    (net (code "23") (name "FB1") (class "Default")
      (node (ref "IC15") (pin "4") (pinfunction "2Y_4") (pintype "bidirectional"))
      (node (ref "Q21") (pin "1") (pinfunction "G_1") (pintype "bidirectional"))
    )
    (net (code "24") (name "FB2") (class "Default")
      (node (ref "IC15") (pin "6") (pinfunction "3Y_6") (pintype "bidirectional"))
      (node (ref "Q22") (pin "1") (pinfunction "G_1") (pintype "bidirectional"))
    )
    (net (code "25") (name "FB3") (class "Default")
      (node (ref "IC15") (pin "8") (pinfunction "4Y_8") (pintype "bidirectional"))
      (node (ref "Q23") (pin "1") (pinfunction "G_1") (pintype "bidirectional"))
    )
    (net (code "26") (name "FB4") (class "Default")
      (node (ref "IC15") (pin "10") (pinfunction "5Y_10") (pintype "bidirectional"))
      (node (ref "Q24") (pin "1") (pinfunction "G_1") (pintype "bidirectional"))
    )
    (net (code "27") (name "FB5") (class "Default")
      (node (ref "IC15") (pin "12") (pinfunction "6Y_12") (pintype "bidirectional"))
      (node (ref "Q25") (pin "1") (pinfunction "G_1") (pintype "bidirectional"))
    )
    (net (code "28") (name "FB6") (class "Default")
      (node (ref "IC16") (pin "2") (pinfunction "1Y_2") (pintype "bidirectional"))
      (node (ref "Q26") (pin "1") (pinfunction "G_1") (pintype "bidirectional"))
    )
    (net (code "29") (name "FB7") (class "Default")
      (node (ref "IC16") (pin "4") (pinfunction "2Y_4") (pintype "bidirectional"))
      (node (ref "Q27") (pin "1") (pinfunction "G_1") (pintype "bidirectional"))
    )
    (net (code "30") (name "FD") (class "Default")
      (node (ref "IC2") (pin "7") (pinfunction "DIS_7") (pintype "input"))
      (node (ref "Q10") (pin "3") (pinfunction "S_3") (pintype "bidirectional"))
      (node (ref "Q11") (pin "3") (pinfunction "S_3") (pintype "bidirectional"))
      (node (ref "Q12") (pin "3") (pinfunction "S_3") (pintype "bidirectional"))
      (node (ref "Q14") (pin "3") (pinfunction "S_3") (pintype "bidirectional"))
      (node (ref "Q15") (pin "3") (pinfunction "S_3") (pintype "bidirectional"))
      (node (ref "Q16") (pin "3") (pinfunction "S_3") (pintype "bidirectional"))
      (node (ref "Q29") (pin "3") (pinfunction "S_3") (pintype "bidirectional"))
      (node (ref "Q9") (pin "3") (pinfunction "S_3") (pintype "bidirectional"))
      (node (ref "RB") (pin "1") (pinfunction "1_1") (pintype "passive"))
    )
    (net (code "31") (name "GND") (class "Default")
      (node (ref "ARDPROMINI1") (pin "GND") (pinfunction "GND_GND") (pintype "bidirectional"))
      (node (ref "ARDPROMINI1") (pin "GND1") (pinfunction "GND1_GND1") (pintype "bidirectional"))
      (node (ref "ARDPROMINI1") (pin "GND2") (pinfunction "GND2_GND2") (pintype "bidirectional"))
      (node (ref "ARDPROMINI1") (pin "GND3") (pinfunction "GND3_GND3") (pintype "bidirectional"))
      (node (ref "ARDPROMINI1") (pin "GRN") (pinfunction "DTR_GRN") (pintype "bidirectional"))
      (node (ref "C1") (pin "2") (pinfunction "2_2") (pintype "passive"))
      (node (ref "C10") (pin "-") (pinfunction "-_-") (pintype "passive"))
      (node (ref "C11") (pin "+") (pinfunction "+_+") (pintype "passive"))
      (node (ref "C2") (pin "2") (pinfunction "2_2") (pintype "passive"))
      (node (ref "C4") (pin "-") (pinfunction "-_-") (pintype "passive"))
      (node (ref "C9") (pin "+") (pinfunction "+_+") (pintype "passive"))
      (node (ref "IC") (pin "2") (pinfunction "-IN_2") (pintype "input"))
      (node (ref "IC") (pin "4") (pinfunction "GND_4") (pintype "power_in"))
      (node (ref "IC1") (pin "3") (pinfunction "NON-INVERTING_INPUT_3") (pintype "bidirectional"))
      (node (ref "IC10") (pin "1") (pinfunction "K_1") (pintype "bidirectional"))
      (node (ref "IC11") (pin "1") (pinfunction "K_1") (pintype "bidirectional"))
      (node (ref "IC12") (pin "6") (pinfunction "INH_6") (pintype "bidirectional"))
      (node (ref "IC12") (pin "7") (pinfunction "GND_1_7") (pintype "bidirectional"))
      (node (ref "IC12") (pin "8") (pinfunction "GND_2_8") (pintype "bidirectional"))
      (node (ref "IC13") (pin "2") (pinfunction "GND_2") (pintype "bidirectional"))
      (node (ref "IC14") (pin "1") (pinfunction "ADJ/GND_1") (pintype "bidirectional"))
      (node (ref "IC15") (pin "7") (pinfunction "GND_7") (pintype "bidirectional"))
      (node (ref "IC16") (pin "7") (pinfunction "GND_7") (pintype "bidirectional"))
      (node (ref "IC2") (pin "1") (pinfunction "GND_1") (pintype "power_in"))
      (node (ref "IC3") (pin "8") (pinfunction "VSS_8") (pintype "power_in"))
      (node (ref "IC4") (pin "1") (pinfunction "K_1") (pintype "bidirectional"))
      (node (ref "IC5") (pin "1") (pinfunction "K_1") (pintype "bidirectional"))
      (node (ref "IC6") (pin "1") (pinfunction "K_1") (pintype "bidirectional"))
      (node (ref "IC7") (pin "1") (pinfunction "K_1") (pintype "bidirectional"))
      (node (ref "IC8") (pin "1") (pinfunction "K_1") (pintype "bidirectional"))
      (node (ref "IC9") (pin "1") (pinfunction "K_1") (pintype "bidirectional"))
      (node (ref "L1") (pin "2") (pinfunction "2_2") (pintype "passive"))
      (node (ref "Q1") (pin "3") (pinfunction "S_3") (pintype "bidirectional"))
      (node (ref "Q17") (pin "3") (pinfunction "S_3") (pintype "bidirectional"))
      (node (ref "Q18") (pin "3") (pinfunction "S_3") (pintype "bidirectional"))
      (node (ref "Q19") (pin "3") (pinfunction "S_3") (pintype "bidirectional"))
      (node (ref "Q2") (pin "3") (pinfunction "S_3") (pintype "bidirectional"))
      (node (ref "Q20") (pin "3") (pinfunction "S_3") (pintype "bidirectional"))
      (node (ref "Q21") (pin "3") (pinfunction "S_3") (pintype "bidirectional"))
      (node (ref "Q22") (pin "3") (pinfunction "S_3") (pintype "bidirectional"))
      (node (ref "Q23") (pin "3") (pinfunction "S_3") (pintype "bidirectional"))
      (node (ref "Q24") (pin "3") (pinfunction "S_3") (pintype "bidirectional"))
      (node (ref "Q25") (pin "3") (pinfunction "S_3") (pintype "bidirectional"))
      (node (ref "Q26") (pin "3") (pinfunction "S_3") (pintype "bidirectional"))
      (node (ref "Q27") (pin "3") (pinfunction "S_3") (pintype "bidirectional"))
      (node (ref "Q3") (pin "3") (pinfunction "S_3") (pintype "bidirectional"))
      (node (ref "Q4") (pin "3") (pinfunction "S_3") (pintype "bidirectional"))
      (node (ref "Q5") (pin "3") (pinfunction "S_3") (pintype "bidirectional"))
      (node (ref "Q6") (pin "3") (pinfunction "S_3") (pintype "bidirectional"))
      (node (ref "Q7") (pin "3") (pinfunction "S_3") (pintype "bidirectional"))
      (node (ref "Q8") (pin "3") (pinfunction "S_3") (pintype "bidirectional"))
      (node (ref "R2") (pin "1") (pinfunction "1_1") (pintype "passive"))
      (node (ref "R27") (pin "1") (pinfunction "1_1") (pintype "passive"))
      (node (ref "R32") (pin "2") (pinfunction "2_2") (pintype "passive"))
      (node (ref "RMS_C1") (pin "2") (pinfunction "2_2") (pintype "passive"))
      (node (ref "RMS_C2") (pin "2") (pinfunction "2_2") (pintype "passive"))
      (node (ref "RMS_C3") (pin "2") (pinfunction "2_2") (pintype "passive"))
      (node (ref "RMS_C4") (pin "2") (pinfunction "2_2") (pintype "passive"))
      (node (ref "RMS_C5") (pin "2") (pinfunction "2_2") (pintype "passive"))
      (node (ref "RMS_C6") (pin "2") (pinfunction "2_2") (pintype "passive"))
      (node (ref "RMS_C7") (pin "2") (pinfunction "2_2") (pintype "passive"))
      (node (ref "RMS_C8") (pin "2") (pinfunction "2_2") (pintype "passive"))
      (node (ref "RU1") (pin "1") (pinfunction "1_1") (pintype "passive"))
      (node (ref "RU2") (pin "1") (pinfunction "1_1") (pintype "passive"))
      (node (ref "RU3") (pin "1") (pinfunction "1_1") (pintype "passive"))
      (node (ref "RUR") (pin "1") (pinfunction "1_1") (pintype "passive"))
      (node (ref "X10") (pin "2") (pinfunction "KL_2") (pintype "passive"))
      (node (ref "X11") (pin "2") (pinfunction "KL_2") (pintype "passive"))
      (node (ref "X2") (pin "4") (pinfunction "KL_4") (pintype "passive"))
      (node (ref "X6") (pin "2") (pinfunction "KL_2") (pintype "passive"))
      (node (ref "X9") (pin "2") (pinfunction "KL_2") (pintype "passive"))
    )
    (net (code "32") (name "GS") (class "Default")
      (node (ref "ARDPROMINI1") (pin "D2") (pinfunction "D2_D2") (pintype "bidirectional"))
      (node (ref "IC3") (pin "14") (pinfunction "GS_14") (pintype "output"))
    )
    (net (code "33") (name "LEDINB") (class "Default")
      (node (ref "IC16") (pin "10") (pinfunction "5Y_10") (pintype "bidirectional"))
      (node (ref "Q19") (pin "1") (pinfunction "G_1") (pintype "bidirectional"))
    )
    (net (code "34") (name "LEDING") (class "Default")
      (node (ref "IC16") (pin "8") (pinfunction "4Y_8") (pintype "bidirectional"))
      (node (ref "Q18") (pin "1") (pinfunction "G_1") (pintype "bidirectional"))
    )
    (net (code "35") (name "LEDINR") (class "Default")
      (node (ref "IC16") (pin "6") (pinfunction "3Y_6") (pintype "bidirectional"))
      (node (ref "Q17") (pin "1") (pinfunction "G_1") (pintype "bidirectional"))
    )
    (net (code "36") (name "LEDPB") (class "Default")
      (node (ref "ARDPROMINI1") (pin "D6") (pinfunction "D6_D6") (pintype "bidirectional"))
      (node (ref "IC16") (pin "11") (pinfunction "5A_11") (pintype "bidirectional"))
    )
    (net (code "37") (name "LEDPG") (class "Default")
      (node (ref "ARDPROMINI1") (pin "D5") (pinfunction "D5_D5") (pintype "bidirectional"))
      (node (ref "IC16") (pin "9") (pinfunction "4A_9") (pintype "bidirectional"))
    )
    (net (code "38") (name "LEDPR") (class "Default")
      (node (ref "ARDPROMINI1") (pin "D3") (pinfunction "D3_D3") (pintype "bidirectional"))
      (node (ref "IC16") (pin "5") (pinfunction "3A_5") (pintype "bidirectional"))
    )
    (net (code "39") (name "LOB") (class "Default")
      (node (ref "Q19") (pin "2") (pinfunction "D_2") (pintype "bidirectional"))
      (node (ref "RL3") (pin "1") (pinfunction "1_1") (pintype "passive"))
      (node (ref "X2") (pin "1") (pinfunction "KL_1") (pintype "passive"))
    )
    (net (code "40") (name "LOG") (class "Default")
      (node (ref "Q18") (pin "2") (pinfunction "D_2") (pintype "bidirectional"))
      (node (ref "RL2") (pin "1") (pinfunction "1_1") (pintype "passive"))
      (node (ref "X2") (pin "2") (pinfunction "KL_2") (pintype "passive"))
    )
    (net (code "41") (name "LOR") (class "Default")
      (node (ref "Q17") (pin "2") (pinfunction "D_2") (pintype "bidirectional"))
      (node (ref "RL1") (pin "1") (pinfunction "1_1") (pintype "passive"))
      (node (ref "X2") (pin "3") (pinfunction "KL_3") (pintype "passive"))
    )
    (net (code "42") (name "MS1") (class "Default")
      (node (ref "IC3") (pin "10") (pinfunction "D0_10") (pintype "input"))
      (node (ref "IC4") (pin "3") (pinfunction "C_3") (pintype "bidirectional"))
      (node (ref "RMS_C1") (pin "1") (pinfunction "1_1") (pintype "passive"))
    )
    (net (code "43") (name "MS2") (class "Default")
      (node (ref "IC3") (pin "11") (pinfunction "D1_11") (pintype "input"))
      (node (ref "IC5") (pin "3") (pinfunction "C_3") (pintype "bidirectional"))
      (node (ref "RMS_C2") (pin "1") (pinfunction "1_1") (pintype "passive"))
    )
    (net (code "44") (name "MS3") (class "Default")
      (node (ref "IC3") (pin "12") (pinfunction "D2_12") (pintype "input"))
      (node (ref "IC6") (pin "3") (pinfunction "C_3") (pintype "bidirectional"))
      (node (ref "RMS_C3") (pin "1") (pinfunction "1_1") (pintype "passive"))
    )
    (net (code "45") (name "MS4") (class "Default")
      (node (ref "IC3") (pin "13") (pinfunction "D3_13") (pintype "input"))
      (node (ref "IC7") (pin "3") (pinfunction "C_3") (pintype "bidirectional"))
      (node (ref "RMS_C4") (pin "1") (pinfunction "1_1") (pintype "passive"))
    )
    (net (code "46") (name "MS5") (class "Default")
      (node (ref "IC3") (pin "1") (pinfunction "D4_1") (pintype "input"))
      (node (ref "IC8") (pin "3") (pinfunction "C_3") (pintype "bidirectional"))
      (node (ref "RMS_C5") (pin "1") (pinfunction "1_1") (pintype "passive"))
    )
    (net (code "47") (name "MS6") (class "Default")
      (node (ref "IC3") (pin "2") (pinfunction "D5_2") (pintype "input"))
      (node (ref "IC9") (pin "3") (pinfunction "C_3") (pintype "bidirectional"))
      (node (ref "RMS_C6") (pin "1") (pinfunction "1_1") (pintype "passive"))
    )
    (net (code "48") (name "MS7") (class "Default")
      (node (ref "IC10") (pin "3") (pinfunction "C_3") (pintype "bidirectional"))
      (node (ref "IC3") (pin "3") (pinfunction "D6_3") (pintype "input"))
      (node (ref "RMS_C7") (pin "1") (pinfunction "1_1") (pintype "passive"))
    )
    (net (code "49") (name "MS8") (class "Default")
      (node (ref "IC11") (pin "3") (pinfunction "C_3") (pintype "bidirectional"))
      (node (ref "IC3") (pin "4") (pinfunction "D7_4") (pintype "input"))
      (node (ref "RMS_C8") (pin "1") (pinfunction "1_1") (pintype "passive"))
    )
    (net (code "50") (name "Net-(C3-Pad+)") (class "Default")
      (node (ref "C3") (pin "+") (pinfunction "+_+") (pintype "passive"))
      (node (ref "R18") (pin "2") (pinfunction "2_2") (pintype "passive"))
    )
    (net (code "51") (name "Net-(C3-Pad-)") (class "Default")
      (node (ref "C3") (pin "-") (pinfunction "-_-") (pintype "passive"))
      (node (ref "IC") (pin "8") (pinfunction "GAIN_8") (pintype "passive"))
    )
    (net (code "52") (name "Net-(C5-Pad-)") (class "Default")
      (node (ref "C5") (pin "-") (pinfunction "-_-") (pintype "passive"))
      (node (ref "R27") (pin "2") (pinfunction "2_2") (pintype "passive"))
    )
    (net (code "53") (name "Net-(C8-Pad2)") (class "Default")
      (node (ref "C8") (pin "2") (pinfunction "2_2") (pintype "passive"))
      (node (ref "S1") (pin "S") (pinfunction "S_S") (pintype "passive"))
    )
    (net (code "54") (name "Net-(IC-+IN)") (class "Default")
      (node (ref "IC") (pin "3") (pinfunction "+IN_3") (pintype "input"))
      (node (ref "X11") (pin "3") (pinfunction "KL_3") (pintype "passive"))
    )
    (net (code "55") (name "Net-(IC-BYPASS)") (class "Default")
      (node (ref "C4") (pin "+") (pinfunction "+_+") (pintype "passive"))
      (node (ref "IC") (pin "7") (pinfunction "BYPASS_7") (pintype "passive"))
    )
    (net (code "56") (name "Net-(IC-GAIN-Pad1)") (class "Default")
      (node (ref "IC") (pin "1") (pinfunction "GAIN_1") (pintype "passive"))
      (node (ref "R18") (pin "1") (pinfunction "1_1") (pintype "passive"))
    )
    (net (code "57") (name "Net-(IC-OUT)") (class "Default")
      (node (ref "C5") (pin "+") (pinfunction "+_+") (pintype "passive"))
      (node (ref "C6") (pin "+") (pinfunction "+_+") (pintype "passive"))
      (node (ref "IC") (pin "5") (pinfunction "OUT_5") (pintype "output"))
    )
    (net (code "58") (name "Net-(IC1-INVERTING_INPUT)") (class "Default")
      (node (ref "C7") (pin "1") (pinfunction "1_1") (pintype "passive"))
      (node (ref "IC1") (pin "2") (pinfunction "INVERTING_INPUT_2") (pintype "bidirectional"))
      (node (ref "R17") (pin "1") (pinfunction "1_1") (pintype "passive"))
      (node (ref "R30") (pin "2") (pinfunction "2_2") (pintype "passive"))
    )
    (net (code "59") (name "Net-(IC1-OUTPUT)") (class "Default")
      (node (ref "C7") (pin "2") (pinfunction "2_2") (pintype "passive"))
      (node (ref "C8") (pin "1") (pinfunction "1_1") (pintype "passive"))
      (node (ref "IC1") (pin "6") (pinfunction "OUTPUT_6") (pintype "bidirectional"))
      (node (ref "R17") (pin "2") (pinfunction "2_2") (pintype "passive"))
      (node (ref "R32") (pin "1") (pinfunction "1_1") (pintype "passive"))
    )
    (net (code "60") (name "Net-(IC2-CV)") (class "Default")
      (node (ref "C2") (pin "1") (pinfunction "1_1") (pintype "passive"))
      (node (ref "IC2") (pin "5") (pinfunction "CV_5") (pintype "input"))
    )
    (net (code "61") (name "Net-(IC2-Q)") (class "Default")
      (node (ref "IC2") (pin "3") (pinfunction "Q_3") (pintype "output"))
      (node (ref "R30") (pin "1") (pinfunction "1_1") (pintype "passive"))
    )
    (net (code "62") (name "Net-(IC2-THR)") (class "Default")
      (node (ref "C1") (pin "1") (pinfunction "1_1") (pintype "passive"))
      (node (ref "IC2") (pin "2") (pinfunction "TR_2") (pintype "input"))
      (node (ref "IC2") (pin "6") (pinfunction "THR_6") (pintype "input"))
      (node (ref "RB") (pin "2") (pinfunction "2_2") (pintype "passive"))
    )
    (net (code "63") (name "Net-(IC4-A)") (class "Default")
      (node (ref "IC4") (pin "2") (pinfunction "A_2") (pintype "bidirectional"))
      (node (ref "R44") (pin "1") (pinfunction "1_1") (pintype "passive"))
    )
    (net (code "64") (name "Net-(IC5-A)") (class "Default")
      (node (ref "IC5") (pin "2") (pinfunction "A_2") (pintype "bidirectional"))
      (node (ref "R41") (pin "1") (pinfunction "1_1") (pintype "passive"))
    )
    (net (code "65") (name "Net-(IC6-A)") (class "Default")
      (node (ref "IC6") (pin "2") (pinfunction "A_2") (pintype "bidirectional"))
      (node (ref "R42") (pin "1") (pinfunction "1_1") (pintype "passive"))
    )
    (net (code "66") (name "Net-(IC7-A)") (class "Default")
      (node (ref "IC7") (pin "2") (pinfunction "A_2") (pintype "bidirectional"))
      (node (ref "R36") (pin "1") (pinfunction "1_1") (pintype "passive"))
    )
    (net (code "67") (name "Net-(IC8-A)") (class "Default")
      (node (ref "IC8") (pin "2") (pinfunction "A_2") (pintype "bidirectional"))
      (node (ref "R37") (pin "1") (pinfunction "1_1") (pintype "passive"))
    )
    (net (code "68") (name "Net-(IC9-A)") (class "Default")
      (node (ref "IC9") (pin "2") (pinfunction "A_2") (pintype "bidirectional"))
      (node (ref "R34") (pin "1") (pinfunction "1_1") (pintype "passive"))
    )
    (net (code "69") (name "Net-(IC10-A)") (class "Default")
      (node (ref "IC10") (pin "2") (pinfunction "A_2") (pintype "bidirectional"))
      (node (ref "R40") (pin "1") (pinfunction "1_1") (pintype "passive"))
    )
    (net (code "70") (name "Net-(IC11-A)") (class "Default")
      (node (ref "IC11") (pin "2") (pinfunction "A_2") (pintype "bidirectional"))
      (node (ref "R31") (pin "1") (pinfunction "1_1") (pintype "passive"))
    )
    (net (code "71") (name "Net-(IC14-OUTPUT)") (class "Default")
      (node (ref "IC14") (pin "2") (pinfunction "OUTPUT_2") (pintype "bidirectional"))
      (node (ref "X6") (pin "1") (pinfunction "KL_1") (pintype "passive"))
    )
    (net (code "72") (name "Net-(Q1-D)") (class "Default")
      (node (ref "Q1") (pin "2") (pinfunction "D_2") (pintype "bidirectional"))
      (node (ref "Q2") (pin "2") (pinfunction "D_2") (pintype "bidirectional"))
      (node (ref "R9") (pin "1") (pinfunction "1_1") (pintype "passive"))
      (node (ref "X1") (pin "2") (pinfunction "KL_2") (pintype "passive"))
    )
    (net (code "73") (name "Net-(Q3-D)") (class "Default")
      (node (ref "Q3") (pin "2") (pinfunction "D_2") (pintype "bidirectional"))
      (node (ref "Q4") (pin "2") (pinfunction "D_2") (pintype "bidirectional"))
      (node (ref "R11") (pin "1") (pinfunction "1_1") (pintype "passive"))
      (node (ref "X3") (pin "2") (pinfunction "KL_2") (pintype "passive"))
    )
    (net (code "74") (name "Net-(Q5-D)") (class "Default")
      (node (ref "Q5") (pin "2") (pinfunction "D_2") (pintype "bidirectional"))
      (node (ref "Q6") (pin "2") (pinfunction "D_2") (pintype "bidirectional"))
      (node (ref "R13") (pin "1") (pinfunction "1_1") (pintype "passive"))
      (node (ref "X5") (pin "2") (pinfunction "KL_2") (pintype "passive"))
    )
    (net (code "75") (name "Net-(Q7-D)") (class "Default")
      (node (ref "Q7") (pin "2") (pinfunction "D_2") (pintype "bidirectional"))
      (node (ref "Q8") (pin "2") (pinfunction "D_2") (pintype "bidirectional"))
      (node (ref "R15") (pin "1") (pinfunction "1_1") (pintype "passive"))
      (node (ref "X7") (pin "2") (pinfunction "KL_2") (pintype "passive"))
    )
    (net (code "76") (name "Net-(Q9-D)") (class "Default")
      (node (ref "Q9") (pin "2") (pinfunction "D_2") (pintype "bidirectional"))
      (node (ref "R19") (pin "1") (pinfunction "1_1") (pintype "passive"))
    )
    (net (code "77") (name "Net-(Q10-D)") (class "Default")
      (node (ref "Q10") (pin "2") (pinfunction "D_2") (pintype "bidirectional"))
      (node (ref "R20") (pin "1") (pinfunction "1_1") (pintype "passive"))
    )
    (net (code "78") (name "Net-(Q11-D)") (class "Default")
      (node (ref "Q11") (pin "2") (pinfunction "D_2") (pintype "bidirectional"))
      (node (ref "R21") (pin "1") (pinfunction "1_1") (pintype "passive"))
    )
    (net (code "79") (name "Net-(Q12-D)") (class "Default")
      (node (ref "Q12") (pin "2") (pinfunction "D_2") (pintype "bidirectional"))
      (node (ref "R22") (pin "1") (pinfunction "1_1") (pintype "passive"))
    )
    (net (code "80") (name "Net-(Q14-D)") (class "Default")
      (node (ref "Q14") (pin "2") (pinfunction "D_2") (pintype "bidirectional"))
      (node (ref "R23") (pin "1") (pinfunction "1_1") (pintype "passive"))
    )
    (net (code "81") (name "Net-(Q15-D)") (class "Default")
      (node (ref "Q15") (pin "2") (pinfunction "D_2") (pintype "bidirectional"))
      (node (ref "R24") (pin "1") (pinfunction "1_1") (pintype "passive"))
    )
    (net (code "82") (name "Net-(Q16-D)") (class "Default")
      (node (ref "Q16") (pin "2") (pinfunction "D_2") (pintype "bidirectional"))
      (node (ref "R25") (pin "1") (pinfunction "1_1") (pintype "passive"))
    )
    (net (code "83") (name "Net-(Q29-D)") (class "Default")
      (node (ref "Q29") (pin "2") (pinfunction "D_2") (pintype "bidirectional"))
      (node (ref "R26") (pin "1") (pinfunction "1_1") (pintype "passive"))
    )
    (net (code "84") (name "Net-(R29-Pad2)") (class "Default")
      (node (ref "R29") (pin "2") (pinfunction "2_2") (pintype "passive"))
      (node (ref "S1") (pin "P") (pinfunction "P_P") (pintype "passive"))
    )
    (net (code "85") (name "Net-(U1-COMPARATORINVERTINGINPUT)") (class "Default")
      (node (ref "R1") (pin "2") (pinfunction "2_2") (pintype "passive"))
      (node (ref "R2") (pin "2") (pinfunction "2_2") (pintype "passive"))
      (node (ref "U1") (pin "5") (pinfunction "COMPARATORINVERTINGINPUT_5") (pintype "passive"))
    )
    (net (code "86") (name "Net-(U1-DRIVERCOLLECTOR)") (class "Default")
      (node (ref "R3") (pin "2") (pinfunction "2_2") (pintype "passive"))
      (node (ref "U1") (pin "1") (pinfunction "SWITCHCOLLECTOR_1") (pintype "passive"))
      (node (ref "U1") (pin "7") (pinfunction "IPK_7") (pintype "passive"))
      (node (ref "U1") (pin "8") (pinfunction "DRIVERCOLLECTOR_8") (pintype "passive"))
    )
    (net (code "87") (name "Net-(U1-GND)") (class "Default")
      (node (ref "C12") (pin "-") (pinfunction "-_-") (pintype "passive"))
      (node (ref "C9") (pin "-") (pinfunction "-_-") (pintype "passive"))
      (node (ref "D1") (pin "A") (pinfunction "A_A") (pintype "passive"))
      (node (ref "L2") (pin "1") (pinfunction "1_1") (pintype "passive"))
      (node (ref "R1") (pin "1") (pinfunction "1_1") (pintype "passive"))
      (node (ref "U1") (pin "4") (pinfunction "GND_4") (pintype "power_in"))
    )
    (net (code "88") (name "Net-(U1-SWITCHEMITTER)") (class "Default")
      (node (ref "D1") (pin "C") (pinfunction "C_C") (pintype "passive"))
      (node (ref "L1") (pin "1") (pinfunction "1_1") (pintype "passive"))
      (node (ref "U1") (pin "2") (pinfunction "SWITCHEMITTER_2") (pintype "passive"))
    )
    (net (code "89") (name "Net-(U1-TIMINGCAPACITOR)") (class "Default")
      (node (ref "C12") (pin "+") (pinfunction "+_+") (pintype "passive"))
      (node (ref "U1") (pin "3") (pinfunction "TIMINGCAPACITOR_3") (pintype "passive"))
    )
    (net (code "90") (name "Net-(X11A-KL)") (class "Default")
      (node (ref "R29") (pin "1") (pinfunction "1_1") (pintype "passive"))
      (node (ref "X11") (pin "1") (pinfunction "KL_1") (pintype "passive"))
    )
    (net (code "91") (name "Net-(X13A-KL)") (class "Default")
      (node (ref "RUR") (pin "2") (pinfunction "2_2") (pintype "passive"))
      (node (ref "X13") (pin "1") (pinfunction "KL_1") (pintype "passive"))
    )
    (net (code "92") (name "Net-(X14A-KL)") (class "Default")
      (node (ref "RU1") (pin "2") (pinfunction "2_2") (pintype "passive"))
      (node (ref "X14") (pin "1") (pinfunction "KL_1") (pintype "passive"))
    )
    (net (code "93") (name "Net-(X15A-KL)") (class "Default")
      (node (ref "RU2") (pin "2") (pinfunction "2_2") (pintype "passive"))
      (node (ref "X15") (pin "1") (pinfunction "KL_1") (pintype "passive"))
    )
    (net (code "94") (name "Net-(X16A-KL)") (class "Default")
      (node (ref "RU3") (pin "2") (pinfunction "2_2") (pintype "passive"))
      (node (ref "X16") (pin "1") (pinfunction "KL_1") (pintype "passive"))
    )
    (net (code "95") (name "Q0") (class "Default")
      (node (ref "ARDPROMINI1") (pin "D10") (pinfunction "D10_D10") (pintype "bidirectional"))
      (node (ref "IC3") (pin "9") (pinfunction "Q0_9") (pintype "output"))
    )
    (net (code "96") (name "Q1") (class "Default")
      (node (ref "ARDPROMINI1") (pin "D11") (pinfunction "D11_D11") (pintype "bidirectional"))
      (node (ref "IC3") (pin "7") (pinfunction "Q1_7") (pintype "output"))
    )
    (net (code "97") (name "Q2") (class "Default")
      (node (ref "ARDPROMINI1") (pin "D12") (pinfunction "D12_D12") (pintype "bidirectional"))
      (node (ref "IC3") (pin "6") (pinfunction "Q2_6") (pintype "output"))
    )
    (net (code "98") (name "SO0") (class "Default")
      (node (ref "ARDPROMINI1") (pin "D7") (pinfunction "D7_D7") (pintype "bidirectional"))
      (node (ref "IC12") (pin "11") (pinfunction "A_11") (pintype "bidirectional"))
    )
    (net (code "99") (name "SO1") (class "Default")
      (node (ref "ARDPROMINI1") (pin "D8") (pinfunction "D8_D8") (pintype "bidirectional"))
      (node (ref "IC12") (pin "10") (pinfunction "B_10") (pintype "bidirectional"))
    )
    (net (code "100") (name "SO2") (class "Default")
      (node (ref "ARDPROMINI1") (pin "D9") (pinfunction "D9_D9") (pintype "bidirectional"))
      (node (ref "IC12") (pin "9") (pinfunction "C_9") (pintype "bidirectional"))
    )
    (net (code "101") (name "S_IN_TEST") (class "Default")
      (node (ref "S1") (pin "O") (pinfunction "O_O") (pintype "passive"))
      (node (ref "X4") (pin "2") (pinfunction "KL_2") (pintype "passive"))
    )
    (net (code "102") (name "S_OUT_TEST") (class "Default")
      (node (ref "C6") (pin "-") (pinfunction "-_-") (pintype "passive"))
      (node (ref "X4") (pin "1") (pinfunction "KL_1") (pintype "passive"))
      (node (ref "X9") (pin "1") (pinfunction "KL_1") (pintype "passive"))
    )
    (net (code "103") (name "UI1") (class "Default")
      (node (ref "ARDPROMINI1") (pin "A0") (pinfunction "A0_A0") (pintype "bidirectional"))
      (node (ref "RU0") (pin "1") (pinfunction "1_1") (pintype "passive"))
      (node (ref "X13") (pin "2") (pinfunction "KL_2") (pintype "passive"))
      (node (ref "X14") (pin "2") (pinfunction "KL_2") (pintype "passive"))
      (node (ref "X15") (pin "2") (pinfunction "KL_2") (pintype "passive"))
      (node (ref "X16") (pin "2") (pinfunction "KL_2") (pintype "passive"))
    )
    (net (code "104") (name "unconnected-(ARDPROMINI1-PadA1)") (class "Default")
      (node (ref "ARDPROMINI1") (pin "A1") (pinfunction "A1_A1") (pintype "bidirectional"))
    )
    (net (code "105") (name "unconnected-(ARDPROMINI1-PadA2)") (class "Default")
      (node (ref "ARDPROMINI1") (pin "A2") (pinfunction "A2_A2") (pintype "bidirectional"))
    )
    (net (code "106") (name "unconnected-(ARDPROMINI1-PadA3)") (class "Default")
      (node (ref "ARDPROMINI1") (pin "A3") (pinfunction "A3_A3") (pintype "bidirectional"))
    )
    (net (code "107") (name "unconnected-(ARDPROMINI1-PadA4)") (class "Default")
      (node (ref "ARDPROMINI1") (pin "A4") (pinfunction "A4_A4") (pintype "bidirectional"))
    )
    (net (code "108") (name "unconnected-(ARDPROMINI1-PadA5)") (class "Default")
      (node (ref "ARDPROMINI1") (pin "A5") (pinfunction "A5_A5") (pintype "bidirectional"))
    )
    (net (code "109") (name "unconnected-(ARDPROMINI1-PadA6)") (class "Default")
      (node (ref "ARDPROMINI1") (pin "A6") (pinfunction "A6_A6") (pintype "bidirectional"))
    )
    (net (code "110") (name "unconnected-(ARDPROMINI1-PadA7)") (class "Default")
      (node (ref "ARDPROMINI1") (pin "A7") (pinfunction "A7_A7") (pintype "bidirectional"))
    )
    (net (code "111") (name "unconnected-(ARDPROMINI1-PadRAW)") (class "Default")
      (node (ref "ARDPROMINI1") (pin "RAW") (pinfunction "RAW_RAW") (pintype "bidirectional"))
    )
    (net (code "112") (name "unconnected-(ARDPROMINI1-PadRST)") (class "Default")
      (node (ref "ARDPROMINI1") (pin "RST") (pinfunction "RST_RST") (pintype "bidirectional"))
    )
    (net (code "113") (name "unconnected-(ARDPROMINI1-PadRST2)") (class "Default")
      (node (ref "ARDPROMINI1") (pin "RST2") (pinfunction "RST2_RST2") (pintype "bidirectional"))
    )
    (net (code "114") (name "unconnected-(ARDPROMINI1-PadRXI)") (class "Default")
      (node (ref "ARDPROMINI1") (pin "RXI") (pinfunction "RXI_RXI") (pintype "bidirectional"))
    )
    (net (code "115") (name "unconnected-(ARDPROMINI1-PadRXI2)") (class "Default")
      (node (ref "ARDPROMINI1") (pin "RXI2") (pinfunction "RXI2_RXI2") (pintype "bidirectional"))
    )
    (net (code "116") (name "unconnected-(ARDPROMINI1-PadTXO)") (class "Default")
      (node (ref "ARDPROMINI1") (pin "TXO") (pinfunction "TXO_TXO") (pintype "bidirectional"))
    )
    (net (code "117") (name "unconnected-(ARDPROMINI1-PadTXO2)") (class "Default")
      (node (ref "ARDPROMINI1") (pin "TXO2") (pinfunction "TXO2_TXO2") (pintype "bidirectional"))
    )
    (net (code "118") (name "unconnected-(IC1-NC-Pad8)") (class "Default")
      (node (ref "IC1") (pin "8") (pinfunction "NC_8") (pintype "no_connect"))
    )
    (net (code "119") (name "unconnected-(IC1-OFFSET_NULL_1-Pad1)") (class "Default")
      (node (ref "IC1") (pin "1") (pinfunction "OFFSET_NULL_1_1") (pintype "bidirectional"))
    )
    (net (code "120") (name "unconnected-(IC1-OFFSET_NULL_2-Pad5)") (class "Default")
      (node (ref "IC1") (pin "5") (pinfunction "OFFSET_NULL_2_5") (pintype "bidirectional"))
    )
    (net (code "121") (name "unconnected-(IC16-6A-Pad13)") (class "Default")
      (node (ref "IC16") (pin "13") (pinfunction "6A_13") (pintype "bidirectional"))
    )
    (net (code "122") (name "unconnected-(IC16-6Y-Pad12)") (class "Default")
      (node (ref "IC16") (pin "12") (pinfunction "6Y_12") (pintype "bidirectional"))
    )
  )
)
